# Sheet2.net
KiCad netlist of a schematic drawn in Altium Designer
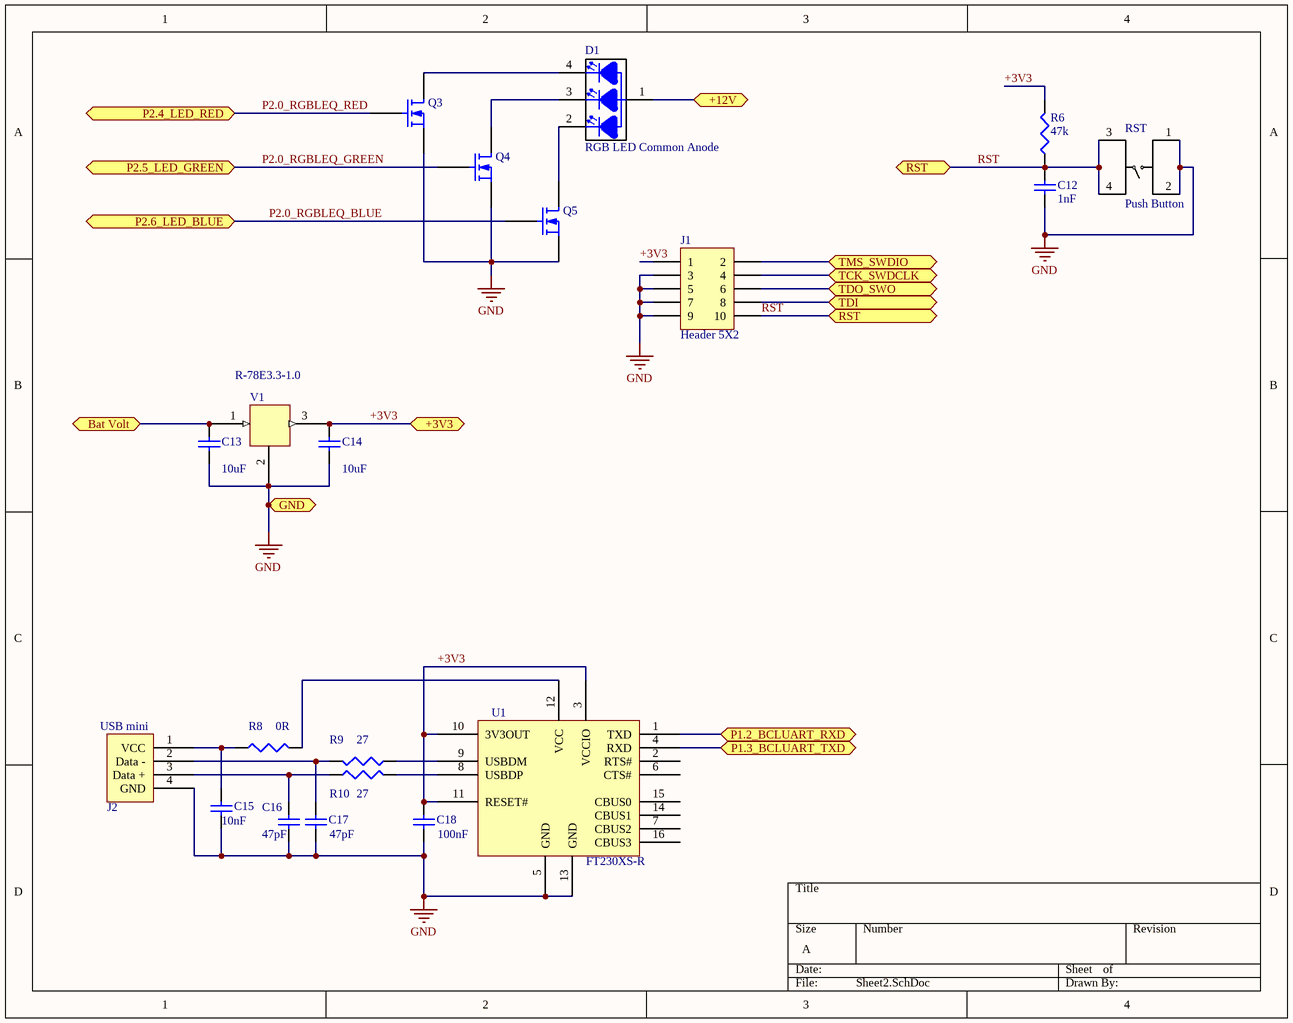
[diagram p0: Sheet2.SchDoc]

(export (version "E")
  (design (tool "Eeschema 10.0.6"))
  (components
    (comp (ref "C12")
      (value "1nF")
      (footprint "0402")
      (description "Capacitor (Semiconductor SIM Model)")
      (fields (field (name "Comment") "Cap Semi") (field (name "PUBLISHER") "Altium Limited"))
      (libsource (lib "Miscellaneous Devices") (part "Cap Semi"))
    )
    (comp (ref "C13")
      (value "10uF")
      (footprint "6-0805_L")
      (description "Capacitor")
      (fields (field (name "Comment") "Cap") (field (name "PUBLISHER") "Altium Limited"))
      (libsource (lib "Miscellaneous Devices") (part "Cap"))
    )
    (comp (ref "C14")
      (value "10uF")
      (footprint "6-0805_L")
      (description "Capacitor")
      (fields (field (name "Comment") "Cap") (field (name "PUBLISHER") "Altium Limited"))
      (libsource (lib "Miscellaneous Devices") (part "Cap"))
    )
    (comp (ref "C15")
      (value "10nF")
      (footprint "0603")
      (description "Capacitor")
      (fields (field (name "Comment") "Cap") (field (name "PUBLISHER") "Altium Limited"))
      (libsource (lib "Miscellaneous Devices") (part "Cap"))
    )
    (comp (ref "C16")
      (value "47pF")
      (footprint "0402")
      (description "Capacitor")
      (fields (field (name "Comment") "Cap") (field (name "PUBLISHER") "Altium Limited"))
      (libsource (lib "Miscellaneous Devices") (part "Cap"))
    )
    (comp (ref "C17")
      (value "47pF")
      (footprint "0402")
      (description "Capacitor")
      (fields (field (name "Comment") "Cap") (field (name "PUBLISHER") "Altium Limited"))
      (libsource (lib "Miscellaneous Devices") (part "Cap"))
    )
    (comp (ref "C18")
      (value "100nF")
      (footprint "0402")
      (description "Capacitor")
      (fields (field (name "Comment") "Cap") (field (name "PUBLISHER") "Altium Limited"))
      (libsource (lib "Miscellaneous Devices") (part "Cap"))
    )
    (comp (ref "D1")
      (value "RGB LED Common Anode")
      (footprint "HDR1X4")
      (libsource (lib "actuatorBoard") (part "RGB LED Common Anode"))
    )
    (comp (ref "J1")
      (value "Header 5X2")
      (footprint "JTAG Header")
      (description "Header, 5-Pin, Dual row")
      (fields (field (name "PUBLISHER") "Altium Limited"))
      (libsource (lib "Miscellaneous Connectors") (part "Header 5X2"))
    )
    (comp (ref "J2")
      (value "USB mini")
      (footprint "USB mini B")
      (libsource (lib "actuatorBoard") (part "USB Port"))
    )
    (comp (ref "Q3")
      (value "MOSFET-N")
      (footprint "DMN1019USN")
      (libsource (lib "actuatorBoard") (part "N-Channel MOSFET"))
    )
    (comp (ref "Q4")
      (value "MOSFET-N")
      (footprint "DMN1019USN")
      (libsource (lib "actuatorBoard") (part "N-Channel MOSFET"))
    )
    (comp (ref "Q5")
      (value "MOSFET-N")
      (footprint "DMN1019USN")
      (libsource (lib "actuatorBoard") (part "N-Channel MOSFET"))
    )
    (comp (ref "R6")
      (value "47k")
      (footprint "J1-0603")
      (description "Resistor")
      (fields (field (name "Comment") "Res3") (field (name "PUBLISHER") "Altium Limited"))
      (libsource (lib "Miscellaneous Devices") (part "Res3"))
    )
    (comp (ref "R8")
      (value "0R")
      (footprint "J1-0603")
      (description "Resistor")
      (fields (field (name "Comment") "Res3") (field (name "PUBLISHER") "Altium Limited"))
      (libsource (lib "Miscellaneous Devices") (part "Res3"))
    )
    (comp (ref "R9")
      (value "27")
      (footprint "J1-0603")
      (description "Resistor")
      (fields (field (name "Comment") "Res3") (field (name "PUBLISHER") "Altium Limited"))
      (libsource (lib "Miscellaneous Devices") (part "Res3"))
    )
    (comp (ref "R10")
      (value "27")
      (footprint "J1-0603")
      (description "Resistor")
      (fields (field (name "Comment") "Res3") (field (name "PUBLISHER") "Altium Limited"))
      (libsource (lib "Miscellaneous Devices") (part "Res3"))
    )
    (comp (ref "RST")
      (value "Push Button")
      (footprint "Push Button")
      (libsource (lib "actuatorBoard") (part "Push Button"))
    )
    (comp (ref "U1")
      (value "FT230XS-R")
      (footprint "SOP64P600X175-16N")
      (libsource (lib "actuatorBoard") (part "FT230XS-R"))
    )
    (comp (ref "V1")
      (value "R-78E3.3-1.0")
      (footprint "R-78E-0.5")
      (description "DC DC converter")
      (libsource (lib "actuatorBoard") (part "R-78E3.3-1.0"))
    )
  )
  (nets
    (net (code "1") (name "/+3V3") (class "Default")
      (node (ref "C14") (pin "2") (pinfunction "2_2") (pintype "passive"))
      (node (ref "C18") (pin "2") (pinfunction "2_2") (pintype "passive"))
      (node (ref "J1") (pin "1") (pinfunction "1_1") (pintype "passive"))
      (node (ref "R6") (pin "2") (pinfunction "2_2") (pintype "passive"))
      (node (ref "U1") (pin "10") (pinfunction "3V3OUT_10") (pintype "passive"))
      (node (ref "U1") (pin "11") (pinfunction "RESET#_11") (pintype "passive"))
      (node (ref "U1") (pin "3") (pinfunction "VCCIO_3") (pintype "passive"))
      (node (ref "V1") (pin "3") (pinfunction "Vout_3") (pintype "output"))
    )
    (net (code "2") (name "/+12V") (class "Default")
      (node (ref "D1") (pin "1") (pinfunction "1_1") (pintype "passive"))
    )
    (net (code "3") (name "/Bat Volt") (class "Default")
      (node (ref "C13") (pin "2") (pinfunction "2_2") (pintype "passive"))
      (node (ref "V1") (pin "1") (pinfunction "Vin_1") (pintype "input"))
    )
    (net (code "4") (name "/P1.2_BCLUART_RXD") (class "Default")
      (node (ref "U1") (pin "1") (pinfunction "TXD_1") (pintype "passive"))
    )
    (net (code "5") (name "/P1.3_BCLUART_TXD") (class "Default")
      (node (ref "U1") (pin "4") (pinfunction "RXD_4") (pintype "passive"))
    )
    (net (code "6") (name "/P2.0_RGBLEQ_BLUE") (class "Default")
      (node (ref "Q5") (pin "1") (pinfunction "G_1") (pintype "passive"))
    )
    (net (code "7") (name "/P2.0_RGBLEQ_GREEN") (class "Default")
      (node (ref "Q4") (pin "1") (pinfunction "G_1") (pintype "passive"))
    )
    (net (code "8") (name "/P2.0_RGBLEQ_RED") (class "Default")
      (node (ref "Q3") (pin "1") (pinfunction "G_1") (pintype "passive"))
    )
    (net (code "9") (name "/RST") (class "Default")
      (node (ref "C12") (pin "2") (pinfunction "2_2") (pintype "passive"))
      (node (ref "J1") (pin "10") (pinfunction "10_10") (pintype "passive"))
      (node (ref "R6") (pin "1") (pinfunction "1_1") (pintype "passive"))
      (node (ref "RST") (pin "3") (pinfunction "3_3") (pintype "passive"))
      (node (ref "RST") (pin "4") (pinfunction "4_4") (pintype "passive"))
    )
    (net (code "10") (name "/TCK_SWDCLK") (class "Default")
      (node (ref "J1") (pin "4") (pinfunction "4_4") (pintype "passive"))
    )
    (net (code "11") (name "/TDI") (class "Default")
      (node (ref "J1") (pin "8") (pinfunction "8_8") (pintype "passive"))
    )
    (net (code "12") (name "/TDO_SWO") (class "Default")
      (node (ref "J1") (pin "6") (pinfunction "6_6") (pintype "passive"))
    )
    (net (code "13") (name "/TMS_SWDIO") (class "Default")
      (node (ref "J1") (pin "2") (pinfunction "2_2") (pintype "passive"))
    )
    (net (code "14") (name "GND") (class "Default")
      (node (ref "C12") (pin "1") (pinfunction "1_1") (pintype "passive"))
      (node (ref "C13") (pin "1") (pinfunction "1_1") (pintype "passive"))
      (node (ref "C14") (pin "1") (pinfunction "1_1") (pintype "passive"))
      (node (ref "C15") (pin "1") (pinfunction "1_1") (pintype "passive"))
      (node (ref "C16") (pin "1") (pinfunction "1_1") (pintype "passive"))
      (node (ref "C17") (pin "1") (pinfunction "1_1") (pintype "passive"))
      (node (ref "C18") (pin "1") (pinfunction "1_1") (pintype "passive"))
      (node (ref "J1") (pin "3") (pinfunction "3_3") (pintype "passive"))
      (node (ref "J1") (pin "5") (pinfunction "5_5") (pintype "passive"))
      (node (ref "J1") (pin "7") (pinfunction "7_7") (pintype "passive"))
      (node (ref "J1") (pin "9") (pinfunction "9_9") (pintype "passive"))
      (node (ref "J2") (pin "4") (pinfunction "GND_4") (pintype "passive"))
      (node (ref "Q3") (pin "2") (pinfunction "S_2") (pintype "passive"))
      (node (ref "Q4") (pin "2") (pinfunction "S_2") (pintype "passive"))
      (node (ref "Q5") (pin "2") (pinfunction "S_2") (pintype "passive"))
      (node (ref "RST") (pin "1") (pinfunction "1_1") (pintype "passive"))
      (node (ref "RST") (pin "2") (pinfunction "2_2") (pintype "passive"))
      (node (ref "U1") (pin "13") (pinfunction "GND_13") (pintype "passive"))
      (node (ref "U1") (pin "5") (pinfunction "GND_5") (pintype "passive"))
      (node (ref "V1") (pin "2") (pinfunction "GND_2") (pintype "passive"))
    )
    (net (code "15") (name "Net-(J2-Data_+)") (class "Default")
      (node (ref "C16") (pin "2") (pinfunction "2_2") (pintype "passive"))
      (node (ref "J2") (pin "3") (pinfunction "Data_+_3") (pintype "passive"))
      (node (ref "R10") (pin "1") (pinfunction "1_1") (pintype "passive"))
    )
    (net (code "16") (name "Net-(J2-Data_-)") (class "Default")
      (node (ref "C17") (pin "2") (pinfunction "2_2") (pintype "passive"))
      (node (ref "J2") (pin "2") (pinfunction "Data_-_2") (pintype "passive"))
      (node (ref "R9") (pin "2") (pinfunction "2_2") (pintype "passive"))
    )
    (net (code "17") (name "Net-(J2-VCC)") (class "Default")
      (node (ref "C15") (pin "2") (pinfunction "2_2") (pintype "passive"))
      (node (ref "J2") (pin "1") (pinfunction "VCC_1") (pintype "passive"))
      (node (ref "R8") (pin "1") (pinfunction "1_1") (pintype "passive"))
    )
    (net (code "18") (name "Net-(Q3-D)") (class "Default")
      (node (ref "D1") (pin "4") (pinfunction "4_4") (pintype "passive"))
      (node (ref "Q3") (pin "3") (pinfunction "D_3") (pintype "passive"))
    )
    (net (code "19") (name "Net-(Q4-D)") (class "Default")
      (node (ref "D1") (pin "3") (pinfunction "3_3") (pintype "passive"))
      (node (ref "Q4") (pin "3") (pinfunction "D_3") (pintype "passive"))
    )
    (net (code "20") (name "Net-(Q5-D)") (class "Default")
      (node (ref "D1") (pin "2") (pinfunction "2_2") (pintype "passive"))
      (node (ref "Q5") (pin "3") (pinfunction "D_3") (pintype "passive"))
    )
    (net (code "21") (name "Net-(U1-USBDM)") (class "Default")
      (node (ref "R9") (pin "1") (pinfunction "1_1") (pintype "passive"))
      (node (ref "U1") (pin "9") (pinfunction "USBDM_9") (pintype "passive"))
    )
    (net (code "22") (name "Net-(U1-USBDP)") (class "Default")
      (node (ref "R10") (pin "2") (pinfunction "2_2") (pintype "passive"))
      (node (ref "U1") (pin "8") (pinfunction "USBDP_8") (pintype "passive"))
    )
    (net (code "23") (name "Net-(U1-VCC)") (class "Default")
      (node (ref "R8") (pin "2") (pinfunction "2_2") (pintype "passive"))
      (node (ref "U1") (pin "12") (pinfunction "VCC_12") (pintype "passive"))
    )
    (net (code "24") (name "unconnected-(U1-CBUS0-Pad15)") (class "Default")
      (node (ref "U1") (pin "15") (pinfunction "CBUS0_15") (pintype "passive"))
    )
    (net (code "25") (name "unconnected-(U1-CBUS1-Pad14)") (class "Default")
      (node (ref "U1") (pin "14") (pinfunction "CBUS1_14") (pintype "passive"))
    )
    (net (code "26") (name "unconnected-(U1-CBUS2-Pad7)") (class "Default")
      (node (ref "U1") (pin "7") (pinfunction "CBUS2_7") (pintype "passive"))
    )
    (net (code "27") (name "unconnected-(U1-CBUS3-Pad16)") (class "Default")
      (node (ref "U1") (pin "16") (pinfunction "CBUS3_16") (pintype "passive"))
    )
    (net (code "28") (name "unconnected-(U1-CTS#-Pad6)") (class "Default")
      (node (ref "U1") (pin "6") (pinfunction "CTS#_6") (pintype "passive"))
    )
    (net (code "29") (name "unconnected-(U1-RTS#-Pad2)") (class "Default")
      (node (ref "U1") (pin "2") (pinfunction "RTS#_2") (pintype "passive"))
    )
  )
)
